# attiny_x5_blink.net
KiCad netlist of a schematic drawn in EAGLE
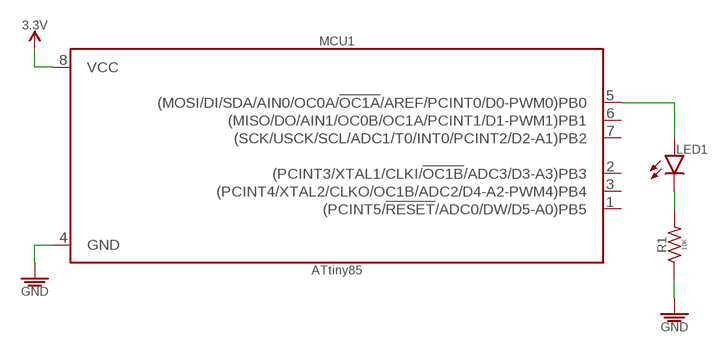
[diagram p0: schematic, sheet 1]

(export (version "E")
  (design (tool "Eeschema 10.0.6"))
  (components
    (comp (ref "LED1")
      (value "LED_PTH_T-1_3/4_5MM_NO-COLOR")
      (footprint "eagle-import:LED_PTH_T-1_3_4_5MM")
      (libsource (lib "eagle-import") (part "LED_PTH_T-1_3/4_5MM_NO-COLOR"))
    )
    (comp (ref "MCU1")
      (value "ATtiny85")
      (footprint "eagle-import:DIP787W45P254L958H533Q8B_DIP-8_ATTINY-X5")
      (fields
        (field (name "MFR") "Microchip Technology")
        (field (name "MPN") "ATTINY85-20PU")
        (field (name "SPICEPREFIX") "X")
      )
      (libsource (lib "eagle-import") (part "ATTINY-X5_DIP-8_ATTINY-85"))
    )
    (comp (ref "R1")
      (value "10K")
      (footprint "eagle-import:RESAD990W55L630D240B")
      (fields (field (name "MFR") "Yageo") (field (name "MPN") "CFR-25JB-52-10K"))
      (libsource (lib "eagle-import") (part "10KΩ_PTH-207/10_1/4W-5%"))
    )
  )
  (nets
    (net (code "1") (name "3.3V") (class "Default")
      (node (ref "MCU1") (pin "8") (pinfunction "VCC_8") (pintype "power_in"))
    )
    (net (code "2") (name "GND") (class "Default")
      (node (ref "MCU1") (pin "4") (pinfunction "GND_4") (pintype "power_in"))
      (node (ref "R1") (pin "1") (pinfunction "1_1") (pintype "passive"))
    )
    (net (code "3") (name "Net-(LED1-PadK)") (class "Default")
      (node (ref "LED1") (pin "K") (pinfunction "K_K") (pintype "passive"))
      (node (ref "R1") (pin "2") (pinfunction "2_2") (pintype "passive"))
    )
    (net (code "4") (name "Net-(MCU1-(MOSI{slash}DI{slash}SDA{slash}AIN0{slash}OC0A{slash}~{OC1A}{slash}AREF{slash}PCINT0{slash}D0-PWM0)PB0)") (class "Default")
      (node (ref "LED1") (pin "A") (pinfunction "A_A") (pintype "passive"))
      (node (ref "MCU1") (pin "5") (pinfunction "(MOSI/DI/SDA/AIN0/OC0A/~{OC1A}/AREF/PCINT0/D0-PWM0)PB0_5") (pintype "bidirectional"))
    )
    (net (code "5") (name "unconnected-(MCU1-(MISO{slash}DO{slash}AIN1{slash}OC0B{slash}OC1A{slash}PCINT1{slash}D1-PWM1)PB1-Pad6)") (class "Default")
      (node (ref "MCU1") (pin "6") (pinfunction "(MISO/DO/AIN1/OC0B/OC1A/PCINT1/D1-PWM1)PB1_6") (pintype "bidirectional"))
    )
    (net (code "6") (name "unconnected-(MCU1-(PCINT3{slash}XTAL1{slash}CLKI{slash}~{OC1B}{slash}ADC3{slash}D3-A3)PB3-Pad2)") (class "Default")
      (node (ref "MCU1") (pin "2") (pinfunction "(PCINT3/XTAL1/CLKI/~{OC1B}/ADC3/D3-A3)PB3_2") (pintype "bidirectional"))
    )
    (net (code "7") (name "unconnected-(MCU1-(PCINT4{slash}XTAL2{slash}CLKO{slash}OC1B{slash}ADC2{slash}D4-A2-PWM4)PB4-Pad3)") (class "Default")
      (node (ref "MCU1") (pin "3") (pinfunction "(PCINT4/XTAL2/CLKO/OC1B/ADC2/D4-A2-PWM4)PB4_3") (pintype "bidirectional"))
    )
    (net (code "8") (name "unconnected-(MCU1-(PCINT5{slash}~{RESET}{slash}ADC0{slash}DW{slash}D5-A0)PB5-Pad1)") (class "Default")
      (node (ref "MCU1") (pin "1") (pinfunction "(PCINT5/~{RESET}/ADC0/DW/D5-A0)PB5_1") (pintype "bidirectional"))
    )
    (net (code "9") (name "unconnected-(MCU1-(SCK{slash}USCK{slash}SCL{slash}ADC1{slash}T0{slash}INT0{slash}PCINT2{slash}D2-A1)PB2-Pad7)") (class "Default")
      (node (ref "MCU1") (pin "7") (pinfunction "(SCK/USCK/SCL/ADC1/T0/INT0/PCINT2/D2-A1)PB2_7") (pintype "bidirectional"))
    )
  )
)
